# ProPrj_Bed_Temp_Regulation_2026-02-19.net
KiCad netlist of a schematic drawn in EasyEDA Pro
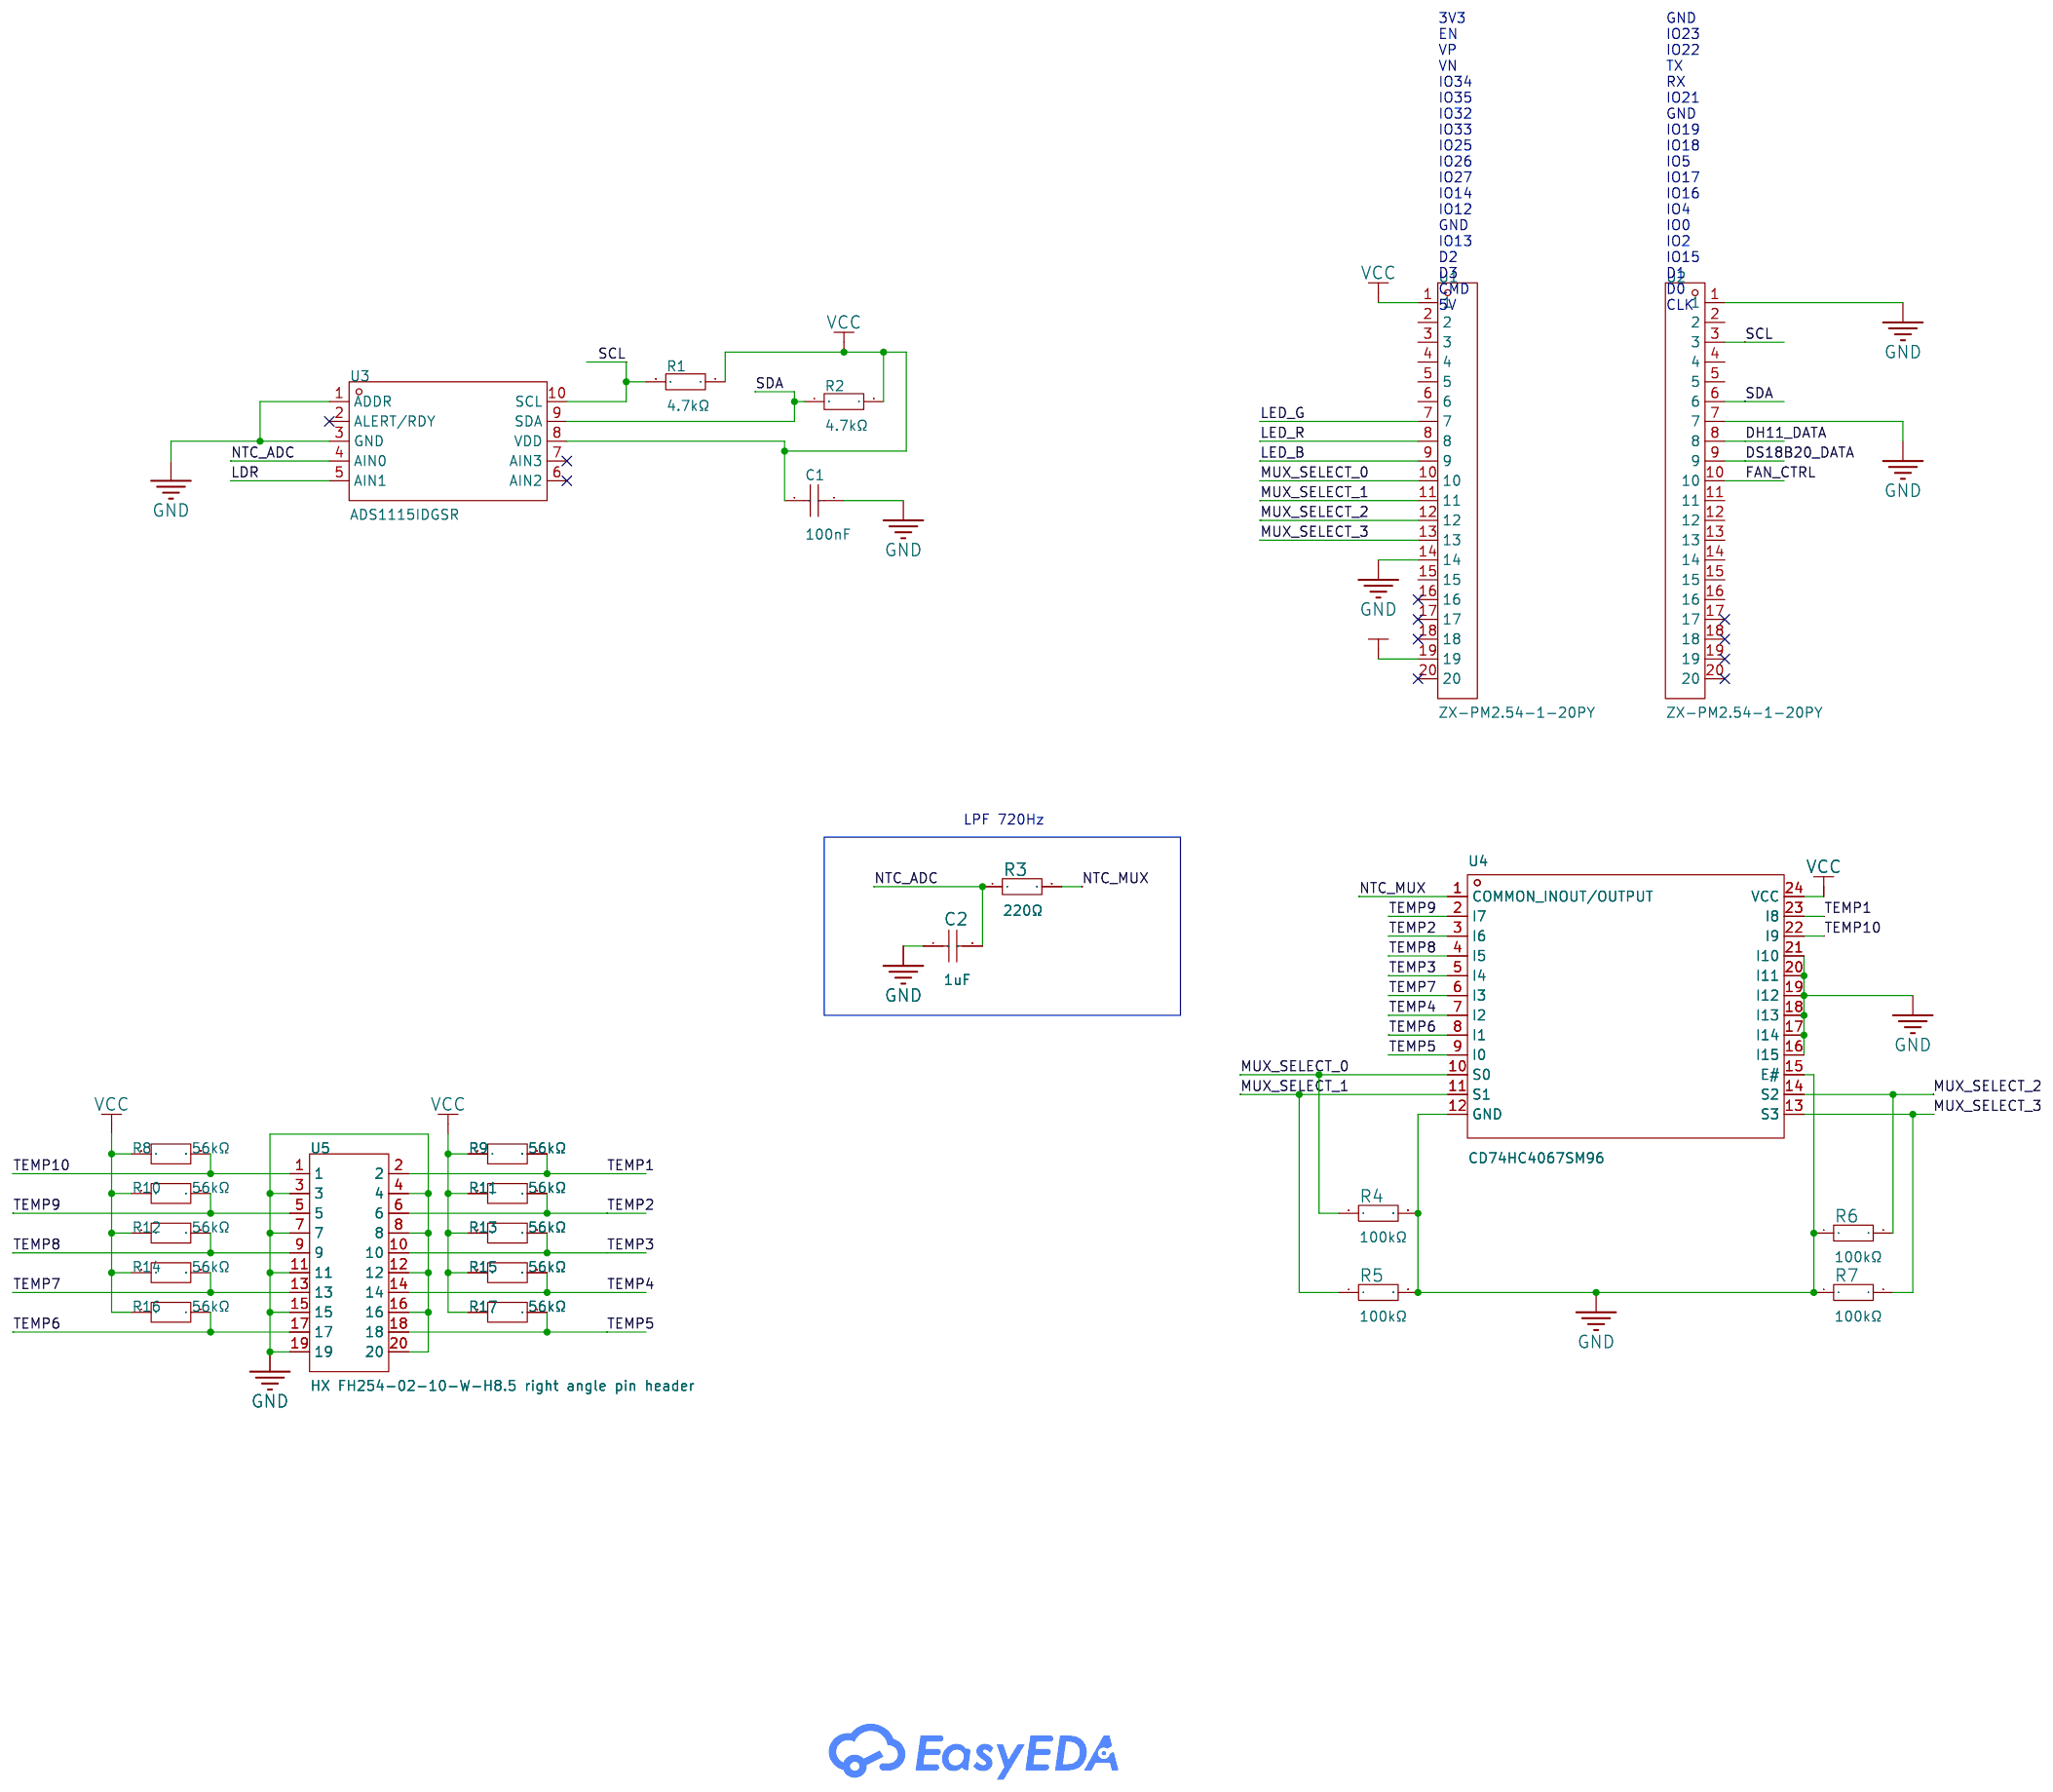
[diagram p0: ADC & ESP]
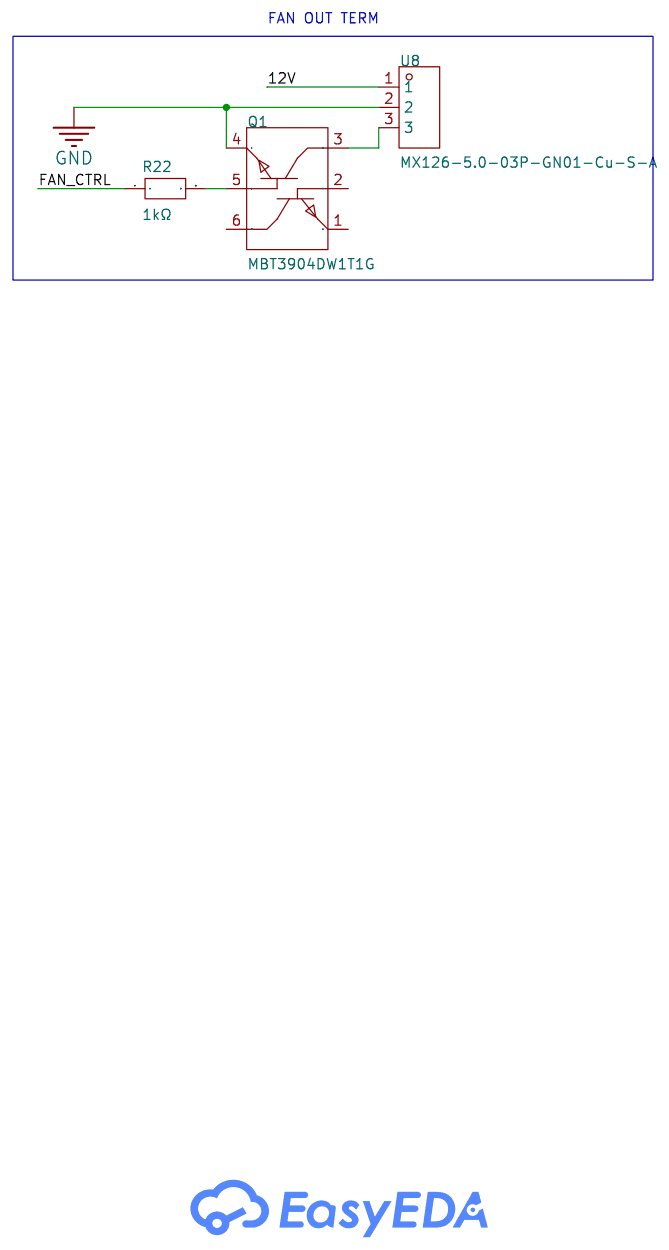
[diagram p1: FAN]
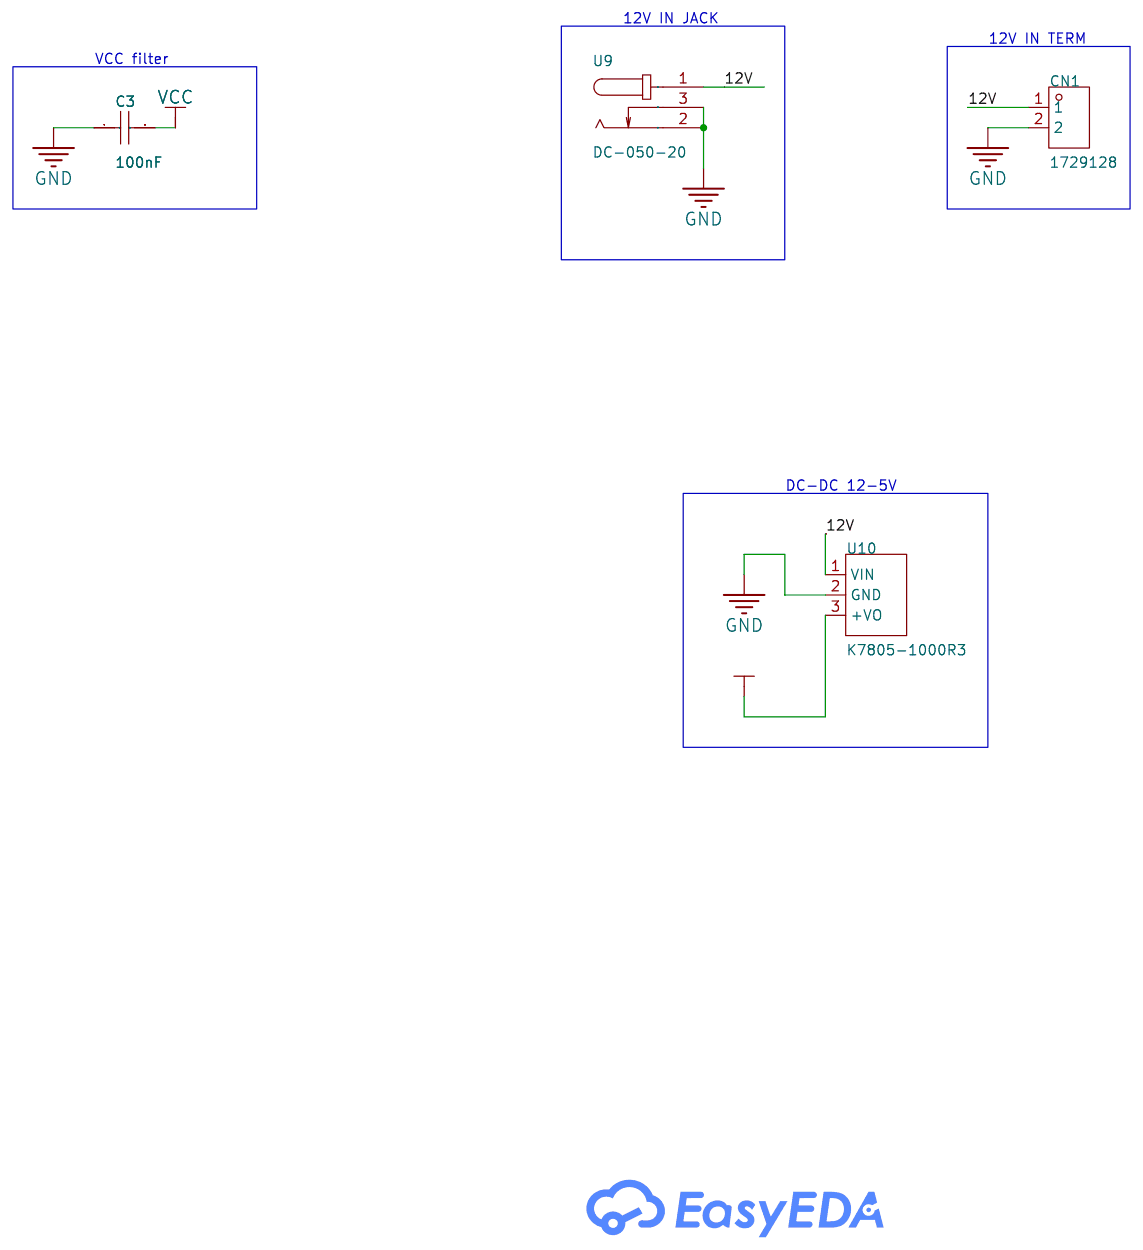
[diagram p2: PWR]
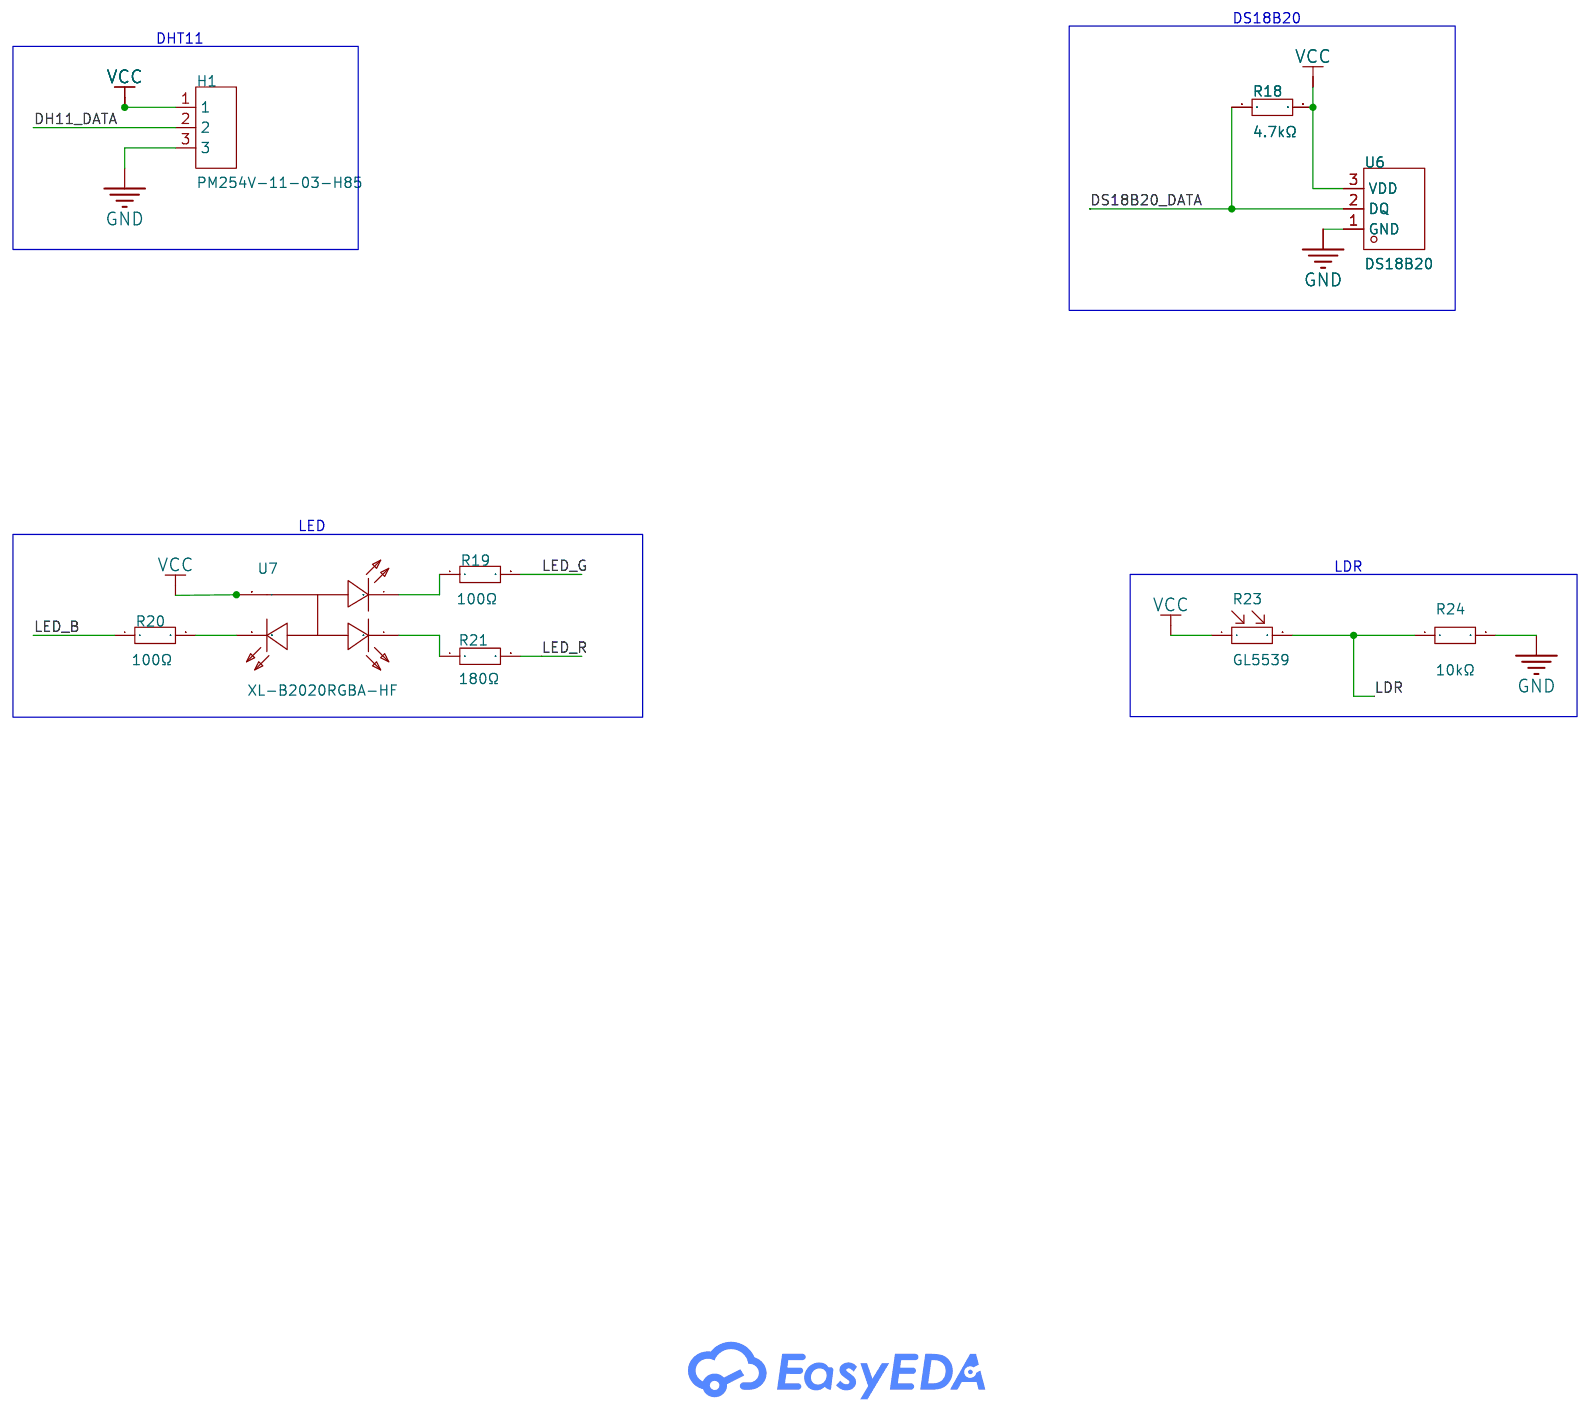
[diagram p3: LED & ENV]

(export (version "E")
  (design (tool "Eeschema 10.0.6"))
  (components
    (comp (ref "C1")
      (value "100nF")
      (footprint "easyedapro:C0805")
      (description "Capacitance:100nF Tolerance:±10% Tolerance:±10% Voltage Rating:100V Temperature Coefficient:X7R")
      (fields
        (field (name "Manufacturer Part") "CL21B104KCFNNNE")
        (field (name "Manufacturer") "SAMSUNG(三星)")
      )
      (libsource (lib "easyedapro") (part "CL21B104KCFNNNE"))
    )
    (comp (ref "C2")
      (value "1uF")
      (footprint "easyedapro:C0805")
      (description "Capacitance:1uF Tolerance:±10% Tolerance:±10% Voltage Rating:50V Temperature Coefficient:X7R")
      (fields
        (field (name "Manufacturer Part") "CL21B105KBFNNNE")
        (field (name "Manufacturer") "SAMSUNG(三星)")
      )
      (libsource (lib "easyedapro") (part "CL21B105KBFNNNE"))
    )
    (comp (ref "R1")
      (value "4.7kΩ")
      (footprint "easyedapro:R0805")
      (fields
        (field (name "Manufacturer Part") "0805W8F4701T5E")
        (field (name "Manufacturer") "UNI-ROYAL(厚声)")
      )
      (libsource (lib "easyedapro") (part "0805W8F4701T5E"))
    )
    (comp (ref "R2")
      (value "4.7kΩ")
      (footprint "easyedapro:R0805")
      (fields
        (field (name "Manufacturer Part") "0805W8F4701T5E")
        (field (name "Manufacturer") "UNI-ROYAL(厚声)")
      )
      (libsource (lib "easyedapro") (part "0805W8F4701T5E"))
    )
    (comp (ref "R3")
      (value "220Ω")
      (footprint "easyedapro:R0805")
      (fields
        (field (name "Manufacturer Part") "0805W8F2200T5E")
        (field (name "Manufacturer") "UNI-ROYAL(厚声)")
      )
      (libsource (lib "easyedapro") (part "0805W8F2200T5E"))
    )
    (comp (ref "R4")
      (value "100kΩ")
      (footprint "easyedapro:R0805")
      (fields
        (field (name "Manufacturer Part") "0805W8F1003T5E")
        (field (name "Manufacturer") "UNI-ROYAL(厚声)")
      )
      (libsource (lib "easyedapro") (part "0805W8F1003T5E_C149504"))
    )
    (comp (ref "R5")
      (value "100kΩ")
      (footprint "easyedapro:R0805")
      (fields
        (field (name "Manufacturer Part") "0805W8F1003T5E")
        (field (name "Manufacturer") "UNI-ROYAL(厚声)")
      )
      (libsource (lib "easyedapro") (part "0805W8F1003T5E_C149504"))
    )
    (comp (ref "R6")
      (value "100kΩ")
      (footprint "easyedapro:R0805")
      (fields
        (field (name "Manufacturer Part") "0805W8F1003T5E")
        (field (name "Manufacturer") "UNI-ROYAL(厚声)")
      )
      (libsource (lib "easyedapro") (part "0805W8F1003T5E_C149504"))
    )
    (comp (ref "R7")
      (value "100kΩ")
      (footprint "easyedapro:R0805")
      (fields
        (field (name "Manufacturer Part") "0805W8F1003T5E")
        (field (name "Manufacturer") "UNI-ROYAL(厚声)")
      )
      (libsource (lib "easyedapro") (part "0805W8F1003T5E_C149504"))
    )
    (comp (ref "R8")
      (value "56kΩ")
      (footprint "easyedapro:R0805")
      (fields
        (field (name "Manufacturer Part") "TC0525B5602T5G")
        (field (name "Manufacturer") "UNI-ROYAL(厚声)")
      )
      (libsource (lib "easyedapro") (part "TC0525B5602T5G"))
    )
    (comp (ref "R9")
      (value "56kΩ")
      (footprint "easyedapro:R0805")
      (fields
        (field (name "Manufacturer Part") "TC0525B5602T5G")
        (field (name "Manufacturer") "UNI-ROYAL(厚声)")
      )
      (libsource (lib "easyedapro") (part "TC0525B5602T5G"))
    )
    (comp (ref "R10")
      (value "56kΩ")
      (footprint "easyedapro:R0805")
      (fields
        (field (name "Manufacturer Part") "TC0525B5602T5G")
        (field (name "Manufacturer") "UNI-ROYAL(厚声)")
      )
      (libsource (lib "easyedapro") (part "TC0525B5602T5G"))
    )
    (comp (ref "R11")
      (value "56kΩ")
      (footprint "easyedapro:R0805")
      (fields
        (field (name "Manufacturer Part") "TC0525B5602T5G")
        (field (name "Manufacturer") "UNI-ROYAL(厚声)")
      )
      (libsource (lib "easyedapro") (part "TC0525B5602T5G"))
    )
    (comp (ref "R12")
      (value "56kΩ")
      (footprint "easyedapro:R0805")
      (fields
        (field (name "Manufacturer Part") "TC0525B5602T5G")
        (field (name "Manufacturer") "UNI-ROYAL(厚声)")
      )
      (libsource (lib "easyedapro") (part "TC0525B5602T5G"))
    )
    (comp (ref "R13")
      (value "56kΩ")
      (footprint "easyedapro:R0805")
      (fields
        (field (name "Manufacturer Part") "TC0525B5602T5G")
        (field (name "Manufacturer") "UNI-ROYAL(厚声)")
      )
      (libsource (lib "easyedapro") (part "TC0525B5602T5G"))
    )
    (comp (ref "R14")
      (value "56kΩ")
      (footprint "easyedapro:R0805")
      (fields
        (field (name "Manufacturer Part") "TC0525B5602T5G")
        (field (name "Manufacturer") "UNI-ROYAL(厚声)")
      )
      (libsource (lib "easyedapro") (part "TC0525B5602T5G"))
    )
    (comp (ref "R15")
      (value "56kΩ")
      (footprint "easyedapro:R0805")
      (fields
        (field (name "Manufacturer Part") "TC0525B5602T5G")
        (field (name "Manufacturer") "UNI-ROYAL(厚声)")
      )
      (libsource (lib "easyedapro") (part "TC0525B5602T5G"))
    )
    (comp (ref "R16")
      (value "56kΩ")
      (footprint "easyedapro:R0805")
      (fields
        (field (name "Manufacturer Part") "TC0525B5602T5G")
        (field (name "Manufacturer") "UNI-ROYAL(厚声)")
      )
      (libsource (lib "easyedapro") (part "TC0525B5602T5G"))
    )
    (comp (ref "R17")
      (value "56kΩ")
      (footprint "easyedapro:R0805")
      (fields
        (field (name "Manufacturer Part") "TC0525B5602T5G")
        (field (name "Manufacturer") "UNI-ROYAL(厚声)")
      )
      (libsource (lib "easyedapro") (part "TC0525B5602T5G"))
    )
    (comp (ref "U1")
      (value "ZX-PM2.54-1-20PY")
      (footprint "easyedapro:HDR-TH_20P-P2.54-V-F")
      (fields (field (name "Manufacturer") "Megastar(兆星)"))
      (libsource (lib "easyedapro") (part "ZX-PM2.54-1-20PY"))
    )
    (comp (ref "U2")
      (value "ZX-PM2.54-1-20PY")
      (footprint "easyedapro:HDR-TH_20P-P2.54-V-F")
      (fields (field (name "Manufacturer") "Megastar(兆星)"))
      (libsource (lib "easyedapro") (part "ZX-PM2.54-1-20PY"))
    )
    (comp (ref "U3")
      (value "ADS1115IDGSR")
      (footprint "easyedapro:MSOP-10_L3.0-W3.0-P0.50-LS5.0-BL")
      (fields (field (name "Manufacturer") "TI(德州仪器)"))
      (libsource (lib "easyedapro") (part "ADS1115IDGSR"))
    )
    (comp (ref "U4")
      (value "CD74HC4067SM96")
      (footprint "easyedapro:SSOP-24_L8.1-W5.3-P0.65-LS7.8-BL")
      (fields (field (name "Manufacturer") "TI(德州仪器)"))
      (libsource (lib "easyedapro") (part "CD74HC4067SM96"))
    )
    (comp (ref "U5")
      (value "HX FH254-02-10-W-H8.5 right angle pin header")
      (footprint "easyedapro:HDR-TH_20P-P2.54-H-F-R2-C10-S2.54-W12.7")
      (fields (field (name "Manufacturer") "hanxia(韩下)"))
      (libsource (lib "easyedapro") (part "HX FH254-02-10-W-H8.5 RIGHT ANGLE PIN HEADER"))
    )
    (comp (ref "Q1")
      (value "MBT3904DW1T1G")
      (footprint "easyedapro:SOT-363_L2.0-W1.3-P0.65-LS2.1-TL")
      (fields (field (name "Manufacturer") "onsemi(安森美)"))
      (libsource (lib "easyedapro") (part "MBT3904DW1T1G"))
    )
    (comp (ref "R22")
      (value "1kΩ")
      (footprint "easyedapro:R0805")
      (fields (field (name "Manufacturer Part") "FRC0805J102 TS") (field (name "Manufacturer") "FOJAN(富捷)"))
      (libsource (lib "easyedapro") (part "FRC0805J102 TS"))
    )
    (comp (ref "U8")
      (value "MX126-5.0-03P-GN01-Cu-S-A")
      (footprint "easyedapro:CONN-TH_3P-P5.00_MAX_MX126-5.0-GN01-03P-CU-S-A")
      (fields (field (name "Manufacturer") "MAX(迈旭)"))
      (libsource (lib "easyedapro") (part "MX126-5.0-GN01-03P-CU-S-A"))
    )
    (comp (ref "C3")
      (value "100nF")
      (footprint "easyedapro:C0805")
      (description "Capacitance:100nF Tolerance:±10% Tolerance:±10% Voltage Rating:100V Temperature Coefficient:X7R")
      (fields
        (field (name "Manufacturer Part") "CL21B104KCFNNNE")
        (field (name "Manufacturer") "SAMSUNG(三星)")
      )
      (libsource (lib "easyedapro") (part "CL21B104KCFNNNE"))
    )
    (comp (ref "CN1")
      (value "1729128")
      (footprint "easyedapro:CONN-TH_2P-P5.08_1729128")
      (fields (field (name "Manufacturer") "Phoenix Contact(菲尼克斯)"))
      (libsource (lib "easyedapro") (part "1729128"))
    )
    (comp (ref "U9")
      (value "DC-050-20")
      (footprint "easyedapro:DC-IN-SMD_DC-050-20A")
      (fields (field (name "Manufacturer") "HanElectricity(瀚源)"))
      (libsource (lib "easyedapro") (part "DC-050-20"))
    )
    (comp (ref "U10")
      (value "K7805-1000R3")
      (footprint "easyedapro:PWRM-TH_YLPTEC_K78XX-1000R3")
      (fields (field (name "Manufacturer") "YLPTEC(易川)"))
      (libsource (lib "easyedapro") (part "K7805-1000R3_C2992391"))
    )
    (comp (ref "H1")
      (value "PM254V-11-03-H85")
      (footprint "easyedapro:HDR-TH_3P-P2.54-V-F")
      (fields (field (name "Manufacturer") "XFCN(兴飞)"))
      (libsource (lib "easyedapro") (part "PM254V-11-03-H85"))
    )
    (comp (ref "R18")
      (value "4.7kΩ")
      (footprint "easyedapro:R0805")
      (fields
        (field (name "Manufacturer Part") "0805W8F4701T5E")
        (field (name "Manufacturer") "UNI-ROYAL(厚声)")
      )
      (libsource (lib "easyedapro") (part "0805W8F4701T5E"))
    )
    (comp (ref "R19")
      (value "100Ω")
      (footprint "easyedapro:R0805")
      (fields
        (field (name "Manufacturer Part") "0805W8F1000T5E")
        (field (name "Manufacturer") "UNI-ROYAL(厚声)")
      )
      (libsource (lib "easyedapro") (part "0805W8F1000T5E"))
    )
    (comp (ref "R20")
      (value "100Ω")
      (footprint "easyedapro:R0805")
      (fields
        (field (name "Manufacturer Part") "0805W8F1000T5E")
        (field (name "Manufacturer") "UNI-ROYAL(厚声)")
      )
      (libsource (lib "easyedapro") (part "0805W8F1000T5E"))
    )
    (comp (ref "R21")
      (value "180Ω")
      (footprint "easyedapro:R0805")
      (fields
        (field (name "Manufacturer Part") "0805W8F1800T5E")
        (field (name "Manufacturer") "UNI-ROYAL(厚声)")
      )
      (libsource (lib "easyedapro") (part "0805W8F1800T5E"))
    )
    (comp (ref "R23")
      (value "GL5539")
      (footprint "easyedapro:RES-TH_L5.1-W4.3-P3.40-D0.5")
      (fields (field (name "Manufacturer") "森霸"))
      (libsource (lib "easyedapro") (part "GL5539"))
    )
    (comp (ref "R24")
      (value "10kΩ")
      (footprint "easyedapro:R0805")
      (fields
        (field (name "Manufacturer Part") "0805W8F1002T5E")
        (field (name "Manufacturer") "UNI-ROYAL(厚声)")
      )
      (libsource (lib "easyedapro") (part "0805W8F1002T5E"))
    )
    (comp (ref "U6")
      (value "DS18B20")
      (footprint "easyedapro:TO-92-3_L4.5-W3.5-P1.27-L")
      (fields (field (name "Manufacturer") "HXY MOSFET(华轩阳电子)"))
      (libsource (lib "easyedapro") (part "DS18B20_C5451632"))
    )
    (comp (ref "U7")
      (value "XL-B2020RGBA-HF")
      (footprint "easyedapro:LED-SMD_4P-L2.1-W2.1-P1.0-BL")
      (fields (field (name "Manufacturer") "XINGLIGHT(成兴光)"))
      (libsource (lib "easyedapro") (part "XL-B2020RGBA-HF"))
    )
  )
  (nets
    (net (code "1") (name "5V") (class "Default")
      (node (ref "U1") (pin "19") (pinfunction "19_19") (pintype "unspecified"))
      (node (ref "U10") (pin "3") (pinfunction "+VO_3") (pintype "unspecified"))
    )
    (net (code "2") (name "12V") (class "Default")
      (node (ref "CN1") (pin "1") (pinfunction "1_1") (pintype "unspecified"))
      (node (ref "U10") (pin "1") (pinfunction "VIN_1") (pintype "unspecified"))
      (node (ref "U8") (pin "1") (pinfunction "1_1") (pintype "unspecified"))
      (node (ref "U9") (pin "1") (pinfunction "1_1") (pintype "unspecified"))
    )
    (net (code "3") (name "DH11_DATA") (class "Default")
      (node (ref "H1") (pin "2") (pinfunction "2_2") (pintype "unspecified"))
      (node (ref "U2") (pin "8") (pinfunction "8_8") (pintype "unspecified"))
    )
    (net (code "4") (name "DS18B20_DATA") (class "Default")
      (node (ref "R18") (pin "1") (pinfunction "1_1") (pintype "input"))
      (node (ref "U2") (pin "9") (pinfunction "9_9") (pintype "unspecified"))
      (node (ref "U6") (pin "2") (pinfunction "DQ_2") (pintype "unspecified"))
    )
    (net (code "5") (name "FAN_CTRL") (class "Default")
      (node (ref "R22") (pin "1") (pinfunction "1_1") (pintype "unspecified"))
      (node (ref "U2") (pin "10") (pinfunction "10_10") (pintype "unspecified"))
    )
    (net (code "6") (name "GND") (class "Default")
      (node (ref "C1") (pin "1") (pinfunction "1_1") (pintype "input"))
      (node (ref "C2") (pin "1") (pinfunction "1_1") (pintype "input"))
      (node (ref "C3") (pin "1") (pinfunction "1_1") (pintype "input"))
      (node (ref "CN1") (pin "2") (pinfunction "2_2") (pintype "unspecified"))
      (node (ref "H1") (pin "3") (pinfunction "3_3") (pintype "unspecified"))
      (node (ref "Q1") (pin "4") (pinfunction "4_4") (pintype "input"))
      (node (ref "R24") (pin "2") (pinfunction "2_2") (pintype "input"))
      (node (ref "R4") (pin "2") (pinfunction "2_2") (pintype "input"))
      (node (ref "R5") (pin "2") (pinfunction "2_2") (pintype "input"))
      (node (ref "R6") (pin "1") (pinfunction "1_1") (pintype "input"))
      (node (ref "R7") (pin "1") (pinfunction "1_1") (pintype "input"))
      (node (ref "U1") (pin "14") (pinfunction "14_14") (pintype "unspecified"))
      (node (ref "U10") (pin "2") (pinfunction "GND_2") (pintype "unspecified"))
      (node (ref "U2") (pin "1") (pinfunction "1_1") (pintype "unspecified"))
      (node (ref "U2") (pin "7") (pinfunction "7_7") (pintype "unspecified"))
      (node (ref "U3") (pin "1") (pinfunction "ADDR_1") (pintype "unspecified"))
      (node (ref "U3") (pin "3") (pinfunction "GND_3") (pintype "unspecified"))
      (node (ref "U4") (pin "12") (pinfunction "GND_12") (pintype "unspecified"))
      (node (ref "U4") (pin "15") (pinfunction "E#_15") (pintype "unspecified"))
      (node (ref "U4") (pin "16") (pinfunction "I15_16") (pintype "unspecified"))
      (node (ref "U4") (pin "17") (pinfunction "I14_17") (pintype "unspecified"))
      (node (ref "U4") (pin "18") (pinfunction "I13_18") (pintype "unspecified"))
      (node (ref "U4") (pin "19") (pinfunction "I12_19") (pintype "unspecified"))
      (node (ref "U4") (pin "20") (pinfunction "I11_20") (pintype "unspecified"))
      (node (ref "U4") (pin "21") (pinfunction "I10_21") (pintype "unspecified"))
      (node (ref "U5") (pin "11") (pinfunction "11_11") (pintype "unspecified"))
      (node (ref "U5") (pin "12") (pinfunction "12_12") (pintype "unspecified"))
      (node (ref "U5") (pin "15") (pinfunction "15_15") (pintype "unspecified"))
      (node (ref "U5") (pin "16") (pinfunction "16_16") (pintype "unspecified"))
      (node (ref "U5") (pin "19") (pinfunction "19_19") (pintype "unspecified"))
      (node (ref "U5") (pin "20") (pinfunction "20_20") (pintype "unspecified"))
      (node (ref "U5") (pin "3") (pinfunction "3_3") (pintype "unspecified"))
      (node (ref "U5") (pin "4") (pinfunction "4_4") (pintype "unspecified"))
      (node (ref "U5") (pin "7") (pinfunction "7_7") (pintype "unspecified"))
      (node (ref "U5") (pin "8") (pinfunction "8_8") (pintype "unspecified"))
      (node (ref "U6") (pin "1") (pinfunction "GND_1") (pintype "unspecified"))
      (node (ref "U8") (pin "2") (pinfunction "2_2") (pintype "unspecified"))
      (node (ref "U9") (pin "2") (pinfunction "2_2") (pintype "unspecified"))
      (node (ref "U9") (pin "3") (pinfunction "3_3") (pintype "unspecified"))
    )
    (net (code "7") (name "LDR") (class "Default")
      (node (ref "R23") (pin "2") (pinfunction "2_2") (pintype "input"))
      (node (ref "R24") (pin "1") (pinfunction "1_1") (pintype "input"))
      (node (ref "U3") (pin "5") (pinfunction "AIN1_5") (pintype "unspecified"))
    )
    (net (code "8") (name "LED_B") (class "Default")
      (node (ref "R20") (pin "1") (pinfunction "1_1") (pintype "input"))
      (node (ref "U1") (pin "9") (pinfunction "9_9") (pintype "unspecified"))
    )
    (net (code "9") (name "LED_G") (class "Default")
      (node (ref "R19") (pin "2") (pinfunction "2_2") (pintype "input"))
      (node (ref "U1") (pin "7") (pinfunction "7_7") (pintype "unspecified"))
    )
    (net (code "10") (name "LED_R") (class "Default")
      (node (ref "R21") (pin "2") (pinfunction "2_2") (pintype "input"))
      (node (ref "U1") (pin "8") (pinfunction "8_8") (pintype "unspecified"))
    )
    (net (code "11") (name "MUX_SELECT_0") (class "Default")
      (node (ref "R4") (pin "1") (pinfunction "1_1") (pintype "input"))
      (node (ref "U1") (pin "10") (pinfunction "10_10") (pintype "unspecified"))
      (node (ref "U4") (pin "10") (pinfunction "S0_10") (pintype "unspecified"))
    )
    (net (code "12") (name "MUX_SELECT_1") (class "Default")
      (node (ref "R5") (pin "1") (pinfunction "1_1") (pintype "input"))
      (node (ref "U1") (pin "11") (pinfunction "11_11") (pintype "unspecified"))
      (node (ref "U4") (pin "11") (pinfunction "S1_11") (pintype "unspecified"))
    )
    (net (code "13") (name "MUX_SELECT_2") (class "Default")
      (node (ref "R6") (pin "2") (pinfunction "2_2") (pintype "input"))
      (node (ref "U1") (pin "12") (pinfunction "12_12") (pintype "unspecified"))
      (node (ref "U4") (pin "14") (pinfunction "S2_14") (pintype "unspecified"))
    )
    (net (code "14") (name "MUX_SELECT_3") (class "Default")
      (node (ref "R7") (pin "2") (pinfunction "2_2") (pintype "input"))
      (node (ref "U1") (pin "13") (pinfunction "13_13") (pintype "unspecified"))
      (node (ref "U4") (pin "13") (pinfunction "S3_13") (pintype "unspecified"))
    )
    (net (code "15") (name "NTC_ADC") (class "Default")
      (node (ref "C2") (pin "2") (pinfunction "2_2") (pintype "input"))
      (node (ref "R3") (pin "1") (pinfunction "1_1") (pintype "input"))
      (node (ref "U3") (pin "4") (pinfunction "AIN0_4") (pintype "unspecified"))
    )
    (net (code "16") (name "NTC_MUX") (class "Default")
      (node (ref "R3") (pin "2") (pinfunction "2_2") (pintype "input"))
      (node (ref "U4") (pin "1") (pinfunction "COMMON_INOUT/OUTPUT_1") (pintype "unspecified"))
    )
    (net (code "17") (name "Net-(Q1-Pad3)") (class "Default")
      (node (ref "Q1") (pin "3") (pinfunction "3_3") (pintype "input"))
      (node (ref "U8") (pin "3") (pinfunction "3_3") (pintype "unspecified"))
    )
    (net (code "18") (name "Net-(Q1-Pad5)") (class "Default")
      (node (ref "Q1") (pin "5") (pinfunction "5_5") (pintype "input"))
      (node (ref "R22") (pin "2") (pinfunction "2_2") (pintype "unspecified"))
    )
    (net (code "19") (name "Net-(R19-Pad1)") (class "Default")
      (node (ref "R19") (pin "1") (pinfunction "1_1") (pintype "input"))
      (node (ref "U7") (pin "4") (pinfunction "C_4") (pintype "unspecified"))
    )
    (net (code "20") (name "Net-(R20-Pad2)") (class "Default")
      (node (ref "R20") (pin "2") (pinfunction "2_2") (pintype "input"))
      (node (ref "U7") (pin "2") (pinfunction "C_2") (pintype "unspecified"))
    )
    (net (code "21") (name "Net-(R21-Pad1)") (class "Default")
      (node (ref "R21") (pin "1") (pinfunction "1_1") (pintype "input"))
      (node (ref "U7") (pin "1") (pinfunction "C_1") (pintype "unspecified"))
    )
    (net (code "22") (name "SCL") (class "Default")
      (node (ref "R1") (pin "2") (pinfunction "2_2") (pintype "input"))
      (node (ref "U2") (pin "3") (pinfunction "3_3") (pintype "unspecified"))
      (node (ref "U3") (pin "10") (pinfunction "SCL_10") (pintype "unspecified"))
    )
    (net (code "23") (name "SDA") (class "Default")
      (node (ref "R2") (pin "1") (pinfunction "1_1") (pintype "input"))
      (node (ref "U2") (pin "6") (pinfunction "6_6") (pintype "unspecified"))
      (node (ref "U3") (pin "9") (pinfunction "SDA_9") (pintype "unspecified"))
    )
    (net (code "24") (name "TEMP1") (class "Default")
      (node (ref "R9") (pin "2") (pinfunction "2_2") (pintype "unspecified"))
      (node (ref "U4") (pin "23") (pinfunction "I8_23") (pintype "unspecified"))
      (node (ref "U5") (pin "2") (pinfunction "2_2") (pintype "unspecified"))
    )
    (net (code "25") (name "TEMP2") (class "Default")
      (node (ref "R11") (pin "2") (pinfunction "2_2") (pintype "unspecified"))
      (node (ref "U4") (pin "3") (pinfunction "I6_3") (pintype "unspecified"))
      (node (ref "U5") (pin "6") (pinfunction "6_6") (pintype "unspecified"))
    )
    (net (code "26") (name "TEMP3") (class "Default")
      (node (ref "R13") (pin "2") (pinfunction "2_2") (pintype "unspecified"))
      (node (ref "U4") (pin "5") (pinfunction "I4_5") (pintype "unspecified"))
      (node (ref "U5") (pin "10") (pinfunction "10_10") (pintype "unspecified"))
    )
    (net (code "27") (name "TEMP4") (class "Default")
      (node (ref "R15") (pin "2") (pinfunction "2_2") (pintype "unspecified"))
      (node (ref "U4") (pin "7") (pinfunction "I2_7") (pintype "unspecified"))
      (node (ref "U5") (pin "14") (pinfunction "14_14") (pintype "unspecified"))
    )
    (net (code "28") (name "TEMP5") (class "Default")
      (node (ref "R17") (pin "2") (pinfunction "2_2") (pintype "unspecified"))
      (node (ref "U4") (pin "9") (pinfunction "I0_9") (pintype "unspecified"))
      (node (ref "U5") (pin "18") (pinfunction "18_18") (pintype "unspecified"))
    )
    (net (code "29") (name "TEMP6") (class "Default")
      (node (ref "R16") (pin "2") (pinfunction "2_2") (pintype "unspecified"))
      (node (ref "U4") (pin "8") (pinfunction "I1_8") (pintype "unspecified"))
      (node (ref "U5") (pin "17") (pinfunction "17_17") (pintype "unspecified"))
    )
    (net (code "30") (name "TEMP7") (class "Default")
      (node (ref "R14") (pin "2") (pinfunction "2_2") (pintype "unspecified"))
      (node (ref "U4") (pin "6") (pinfunction "I3_6") (pintype "unspecified"))
      (node (ref "U5") (pin "13") (pinfunction "13_13") (pintype "unspecified"))
    )
    (net (code "31") (name "TEMP8") (class "Default")
      (node (ref "R12") (pin "2") (pinfunction "2_2") (pintype "unspecified"))
      (node (ref "U4") (pin "4") (pinfunction "I5_4") (pintype "unspecified"))
      (node (ref "U5") (pin "9") (pinfunction "9_9") (pintype "unspecified"))
    )
    (net (code "32") (name "TEMP9") (class "Default")
      (node (ref "R10") (pin "2") (pinfunction "2_2") (pintype "unspecified"))
      (node (ref "U4") (pin "2") (pinfunction "I7_2") (pintype "unspecified"))
      (node (ref "U5") (pin "5") (pinfunction "5_5") (pintype "unspecified"))
    )
    (net (code "33") (name "TEMP10") (class "Default")
      (node (ref "R8") (pin "2") (pinfunction "2_2") (pintype "unspecified"))
      (node (ref "U4") (pin "22") (pinfunction "I9_22") (pintype "unspecified"))
      (node (ref "U5") (pin "1") (pinfunction "1_1") (pintype "unspecified"))
    )
    (net (code "34") (name "VCC") (class "Default")
      (node (ref "C1") (pin "2") (pinfunction "2_2") (pintype "input"))
      (node (ref "C3") (pin "2") (pinfunction "2_2") (pintype "input"))
      (node (ref "H1") (pin "1") (pinfunction "1_1") (pintype "unspecified"))
      (node (ref "R1") (pin "1") (pinfunction "1_1") (pintype "input"))
      (node (ref "R10") (pin "1") (pinfunction "1_1") (pintype "unspecified"))
      (node (ref "R11") (pin "1") (pinfunction "1_1") (pintype "unspecified"))
      (node (ref "R12") (pin "1") (pinfunction "1_1") (pintype "unspecified"))
      (node (ref "R13") (pin "1") (pinfunction "1_1") (pintype "unspecified"))
      (node (ref "R14") (pin "1") (pinfunction "1_1") (pintype "unspecified"))
      (node (ref "R15") (pin "1") (pinfunction "1_1") (pintype "unspecified"))
      (node (ref "R16") (pin "1") (pinfunction "1_1") (pintype "unspecified"))
      (node (ref "R17") (pin "1") (pinfunction "1_1") (pintype "unspecified"))
      (node (ref "R18") (pin "2") (pinfunction "2_2") (pintype "input"))
      (node (ref "R2") (pin "2") (pinfunction "2_2") (pintype "input"))
      (node (ref "R23") (pin "1") (pinfunction "1_1") (pintype "input"))
      (node (ref "R8") (pin "1") (pinfunction "1_1") (pintype "unspecified"))
      (node (ref "R9") (pin "1") (pinfunction "1_1") (pintype "unspecified"))
      (node (ref "U1") (pin "1") (pinfunction "1_1") (pintype "unspecified"))
      (node (ref "U3") (pin "8") (pinfunction "VDD_8") (pintype "unspecified"))
      (node (ref "U4") (pin "24") (pinfunction "VCC_24") (pintype "unspecified"))
      (node (ref "U6") (pin "3") (pinfunction "VDD_3") (pintype "unspecified"))
      (node (ref "U7") (pin "3") (pinfunction "A_3") (pintype "unspecified"))
    )
    (net (code "35") (name "unconnected-(Q1-Pad1)") (class "Default")
      (node (ref "Q1") (pin "1") (pinfunction "1_1") (pintype "input"))
    )
    (net (code "36") (name "unconnected-(Q1-Pad2)") (class "Default")
      (node (ref "Q1") (pin "2") (pinfunction "2_2") (pintype "input"))
    )
    (net (code "37") (name "unconnected-(Q1-Pad6)") (class "Default")
      (node (ref "Q1") (pin "6") (pinfunction "6_6") (pintype "input"))
    )
    (net (code "38") (name "unconnected-(U1-Pad2)") (class "Default")
      (node (ref "U1") (pin "2") (pinfunction "2_2") (pintype "unspecified"))
    )
    (net (code "39") (name "unconnected-(U1-Pad3)") (class "Default")
      (node (ref "U1") (pin "3") (pinfunction "3_3") (pintype "unspecified"))
    )
    (net (code "40") (name "unconnected-(U1-Pad4)") (class "Default")
      (node (ref "U1") (pin "4") (pinfunction "4_4") (pintype "unspecified"))
    )
    (net (code "41") (name "unconnected-(U1-Pad5)") (class "Default")
      (node (ref "U1") (pin "5") (pinfunction "5_5") (pintype "unspecified"))
    )
    (net (code "42") (name "unconnected-(U1-Pad6)") (class "Default")
      (node (ref "U1") (pin "6") (pinfunction "6_6") (pintype "unspecified"))
    )
    (net (code "43") (name "unconnected-(U1-Pad15)") (class "Default")
      (node (ref "U1") (pin "15") (pinfunction "15_15") (pintype "unspecified"))
    )
    (net (code "44") (name "unconnected-(U1-Pad16)") (class "Default")
      (node (ref "U1") (pin "16") (pinfunction "16_16") (pintype "unspecified+no_connect"))
    )
    (net (code "45") (name "unconnected-(U1-Pad17)") (class "Default")
      (node (ref "U1") (pin "17") (pinfunction "17_17") (pintype "unspecified+no_connect"))
    )
    (net (code "46") (name "unconnected-(U1-Pad18)") (class "Default")
      (node (ref "U1") (pin "18") (pinfunction "18_18") (pintype "unspecified+no_connect"))
    )
    (net (code "47") (name "unconnected-(U1-Pad20)") (class "Default")
      (node (ref "U1") (pin "20") (pinfunction "20_20") (pintype "unspecified+no_connect"))
    )
    (net (code "48") (name "unconnected-(U2-Pad2)") (class "Default")
      (node (ref "U2") (pin "2") (pinfunction "2_2") (pintype "unspecified"))
    )
    (net (code "49") (name "unconnected-(U2-Pad4)") (class "Default")
      (node (ref "U2") (pin "4") (pinfunction "4_4") (pintype "unspecified"))
    )
    (net (code "50") (name "unconnected-(U2-Pad5)") (class "Default")
      (node (ref "U2") (pin "5") (pinfunction "5_5") (pintype "unspecified"))
    )
    (net (code "51") (name "unconnected-(U2-Pad11)") (class "Default")
      (node (ref "U2") (pin "11") (pinfunction "11_11") (pintype "unspecified"))
    )
    (net (code "52") (name "unconnected-(U2-Pad12)") (class "Default")
      (node (ref "U2") (pin "12") (pinfunction "12_12") (pintype "unspecified"))
    )
    (net (code "53") (name "unconnected-(U2-Pad13)") (class "Default")
      (node (ref "U2") (pin "13") (pinfunction "13_13") (pintype "unspecified"))
    )
    (net (code "54") (name "unconnected-(U2-Pad14)") (class "Default")
      (node (ref "U2") (pin "14") (pinfunction "14_14") (pintype "unspecified"))
    )
    (net (code "55") (name "unconnected-(U2-Pad15)") (class "Default")
      (node (ref "U2") (pin "15") (pinfunction "15_15") (pintype "unspecified"))
    )
    (net (code "56") (name "unconnected-(U2-Pad16)") (class "Default")
      (node (ref "U2") (pin "16") (pinfunction "16_16") (pintype "unspecified"))
    )
    (net (code "57") (name "unconnected-(U2-Pad17)") (class "Default")
      (node (ref "U2") (pin "17") (pinfunction "17_17") (pintype "unspecified+no_connect"))
    )
    (net (code "58") (name "unconnected-(U2-Pad18)") (class "Default")
      (node (ref "U2") (pin "18") (pinfunction "18_18") (pintype "unspecified+no_connect"))
    )
    (net (code "59") (name "unconnected-(U2-Pad19)") (class "Default")
      (node (ref "U2") (pin "19") (pinfunction "19_19") (pintype "unspecified+no_connect"))
    )
    (net (code "60") (name "unconnected-(U2-Pad20)") (class "Default")
      (node (ref "U2") (pin "20") (pinfunction "20_20") (pintype "unspecified+no_connect"))
    )
    (net (code "61") (name "unconnected-(U3-AIN2-Pad6)") (class "Default")
      (node (ref "U3") (pin "6") (pinfunction "AIN2_6") (pintype "unspecified+no_connect"))
    )
    (net (code "62") (name "unconnected-(U3-AIN3-Pad7)") (class "Default")
      (node (ref "U3") (pin "7") (pinfunction "AIN3_7") (pintype "unspecified+no_connect"))
    )
    (net (code "63") (name "unconnected-(U3-ALERT{slash}RDY-Pad2)") (class "Default")
      (node (ref "U3") (pin "2") (pinfunction "ALERT/RDY_2") (pintype "unspecified+no_connect"))
    )
  )
)
